# F_-V1.net
KiCad netlist of a schematic drawn in Altium Designer
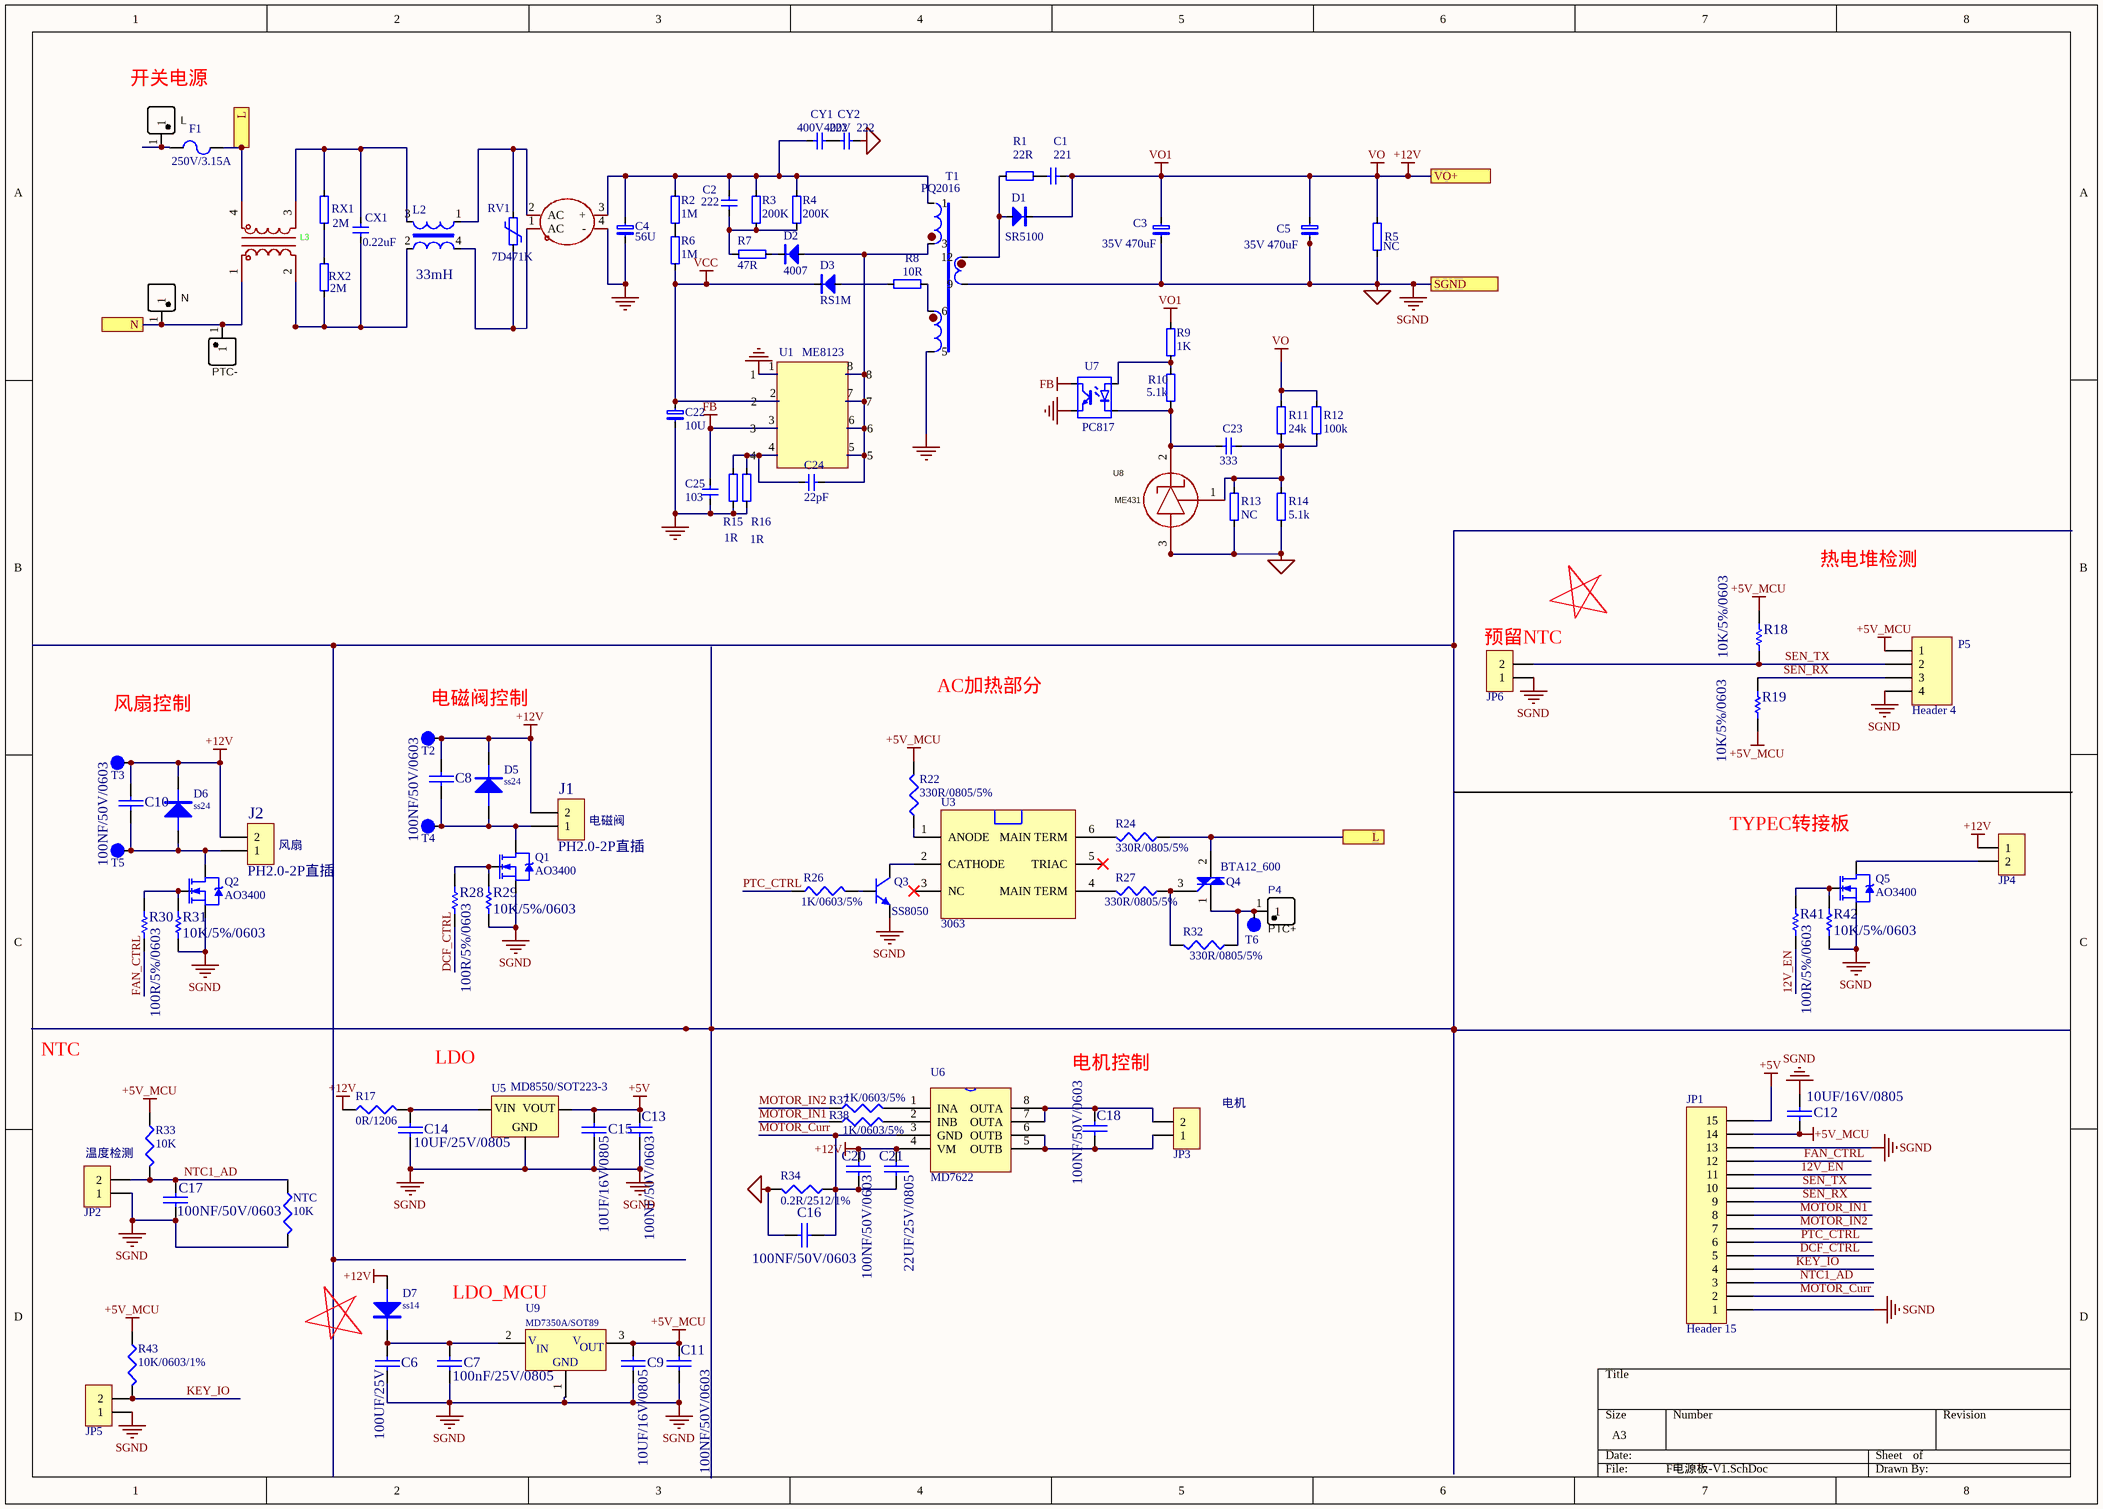
[diagram p0: F电源板-V1.SchDoc]

(export (version "E")
  (design (tool "Eeschema 10.0.6"))
  (components
    (comp (ref "BD1")
      (value "DB107S")
      (footprint "DBS_L8.4-W6.4-P5.10-LS10.2-BL")
      (fields (field (name "MANUFACTURER") "Hottech(合科泰)"))
      (libsource (lib "altium-import") (part "root_2_mirrored_DB107S_C190797_"))
    )
    (comp (ref "C1") (value "221") (footprint "1206c") (description "C？") (libsource (lib "*") (part "C.2")))
    (comp (ref "C2") (value "222") (footprint "1206c") (description "C？") (libsource (lib "*") (part "C.2")))
    (comp (ref "C3")
      (value "35V 470uF")
      (footprint "CAP 5.0*10*16")
      (description "C?")
      (libsource (lib "*") (part "CB.2"))
    )
    (comp (ref "C4")
      (value "56U")
      (footprint "CAP 7.5*16*25")
      (description "C?")
      (libsource (lib "*") (part "CB.2"))
    )
    (comp (ref "C5")
      (value "35V 470uF")
      (footprint "CAP 5.0*10*16")
      (description "C?")
      (libsource (lib "*") (part "CB.2"))
    )
    (comp (ref "C6")
      (value "100UF/25V")
      (footprint "CAP 2.5*5*11")
      (libsource (lib "eric20140112") (part "CAPB"))
    )
    (comp (ref "C7")
      (value "100nF/25V/0805")
      (footprint "C 0805_L")
      (libsource (lib "eric20140112") (part "CAPB"))
    )
    (comp (ref "C8")
      (value "100NF/50V/0603")
      (footprint "C 0603_L")
      (libsource (lib "eric20140112") (part "CAPB"))
    )
    (comp (ref "C9")
      (value "10UF/16V/0805")
      (footprint "C 0805_L")
      (libsource (lib "eric20140112") (part "CAPB"))
    )
    (comp (ref "C10")
      (value "100NF/50V/0603")
      (footprint "C 0603_L")
      (libsource (lib "eric20140112") (part "CAPB"))
    )
    (comp (ref "C11")
      (value "100NF/50V/0603")
      (footprint "C 0603_L")
      (libsource (lib "eric20140112") (part "CAPB"))
    )
    (comp (ref "C12")
      (value "10UF/16V/0805")
      (footprint "C 0805_L")
      (libsource (lib "eric20140112") (part "CAPB"))
    )
    (comp (ref "C13")
      (value "100NF/50V/0603")
      (footprint "C 0603_L")
      (libsource (lib "eric20140112") (part "CAPB"))
    )
    (comp (ref "C14")
      (value "10UF/25V/0805")
      (footprint "C 0805_L")
      (libsource (lib "eric20140112") (part "CAPB"))
    )
    (comp (ref "C15")
      (value "10UF/16V/0805")
      (footprint "C 0805_L")
      (libsource (lib "eric20140112") (part "CAPB"))
    )
    (comp (ref "C16")
      (value "100NF/50V/0603")
      (footprint "C 0603_L")
      (libsource (lib "eric20140112") (part "CAPB"))
    )
    (comp (ref "C17")
      (value "100NF/50V/0603")
      (footprint "C 0603_L")
      (libsource (lib "eric20140112") (part "CAPB"))
    )
    (comp (ref "C18")
      (value "100NF/50V/0603")
      (footprint "C 0603_L")
      (libsource (lib "eric20140112") (part "CAPB"))
    )
    (comp (ref "C20")
      (value "100NF/50V/0603")
      (footprint "C 0603_L")
      (libsource (lib "eric20140112") (part "CAPB"))
    )
    (comp (ref "C21")
      (value "22UF/25V/0805")
      (footprint "0805C-S")
      (libsource (lib "eric20140112") (part "CAPB"))
    )
    (comp (ref "C22")
      (value "10U")
      (footprint "CAP 2.5*5*11 - BK")
      (description "C?")
      (libsource (lib "*") (part "CB.2"))
    )
    (comp (ref "C23") (value "333") (footprint "0805C") (description "C？") (libsource (lib "*") (part "C.2")))
    (comp (ref "C24")
      (value "22pF")
      (footprint "0805C")
      (description "C？")
      (libsource (lib "*") (part "C.2"))
    )
    (comp (ref "C25") (value "103") (footprint "0805C") (description "C？") (libsource (lib "*") (part "C.2")))
    (comp (ref "CX1")
      (value "0.22uF")
      (footprint "CAP-TH_L13.0-W6.0-P10.00-D1.2")
      (description "C？")
      (libsource (lib "*") (part "C.2"))
    )
    (comp (ref "CY1")
      (value "400V  222")
      (footprint "CY2-P10*4.7")
      (description "C？")
      (libsource (lib "*") (part "C.2"))
    )
    (comp (ref "CY2")
      (value "400V  222")
      (footprint "CY2-P10*4.7")
      (description "C？")
      (libsource (lib "*") (part "C.2"))
    )
    (comp (ref "D1") (value "SR5100") (footprint "do-27") (libsource (lib "*") (part "D.2")))
    (comp (ref "D2") (value "4007") (footprint "SMA") (libsource (lib "*") (part "D.2")))
    (comp (ref "D3") (value "RS1M") (footprint "SMA") (libsource (lib "*") (part "D.2")))
    (comp (ref "D5") (value "ss24") (footprint "SOD-123") (libsource (lib "eric20140112") (part "DIODE")))
    (comp (ref "D6") (value "ss24") (footprint "SOD-123") (libsource (lib "eric20140112") (part "DIODE")))
    (comp (ref "D7") (value "ss14") (footprint "SOD-123") (libsource (lib "eric20140112") (part "DIODE")))
    (comp (ref "F1") (value "250V/3.15A") (footprint "MST8*4") (libsource (lib "*") (part "FUSE")))
    (comp (ref "J1")
      (value "PH2.0-2P直插")
      (footprint "PH2.0-LI-2P")
      (libsource (lib "eric20140112") (part "CON2"))
    )
    (comp (ref "J2")
      (value "PH2.0-2P直插")
      (footprint "PH2.0-LI-2P")
      (libsource (lib "eric20140112") (part "CON2"))
    )
    (comp (ref "JP1")
      (value "Header 15")
      (footprint "FPC-SMD_15P-P1.00_XUNPU_FPC-1.0FX-15PWCR-H20")
      (description "Header, 15-Pin")
      (fields (field (name "PUBLISHER") "Altium Limited"))
      (libsource (lib "Miscellaneous Connectors") (part "Header 15"))
    )
    (comp (ref "JP2")
      (value "HDR-1X2")
      (footprint "PH2.0-LI-2P")
      (description "2P接插件")
      (fields (field (name "版权归属") "源创客"))
      (libsource (lib "4.4   - 接插件-脚距2.0") (part "Header 2"))
    )
    (comp (ref "JP3")
      (value "HDR-1X2")
      (footprint "PH2.0-LI-2P")
      (description "2P接插件")
      (fields (field (name "版权归属") "源创客"))
      (libsource (lib "") (part "Header 2_2"))
    )
    (comp (ref "JP4")
      (value "HDR-1X2")
      (footprint "PH2.0-LI-2P")
      (description "2P接插件")
      (fields (field (name "版权归属") "源创客"))
      (libsource (lib "") (part "Header 2_1"))
    )
    (comp (ref "JP5")
      (value "HDR-1X2")
      (footprint "PH2.0-LI-2P")
      (description "2P接插件")
      (fields (field (name "版权归属") "源创客"))
      (libsource (lib "4.4   - 接插件-脚距2.0") (part "Header 2"))
    )
    (comp (ref "JP6")
      (value "HDR-1X2")
      (footprint "PH2.0-LI-2P")
      (description "2P接插件")
      (fields (field (name "版权归属") "源创客"))
      (libsource (lib "4.4   - 接插件-脚距2.0") (part "Header 2"))
    )
    (comp (ref "L2") (value "~") (footprint "UU9.8") (libsource (lib "*") (part "LC.6")))
    (comp (ref "L3")
      (value "PDMCAT953-501MLN")
      (footprint "IND-TH_4P-L12.0-W6.0_PDMCAT953-501MLN")
      (fields (field (name "MANUFACTURER") "PROD(谱罗德)"))
      (libsource (lib "altium-import") (part "root_1_PDMCAT953-501MLN_"))
    )
    (comp (ref "NTC") (value "10K") (footprint "R 0603_L") (libsource (lib "DXPsch") (part "R")))
    (comp (ref "P1")
      (value "L")
      (footprint "4.8*0.8")
      (fields
        (field (name "BOM_SUPPLIER PART") "C9900007423")
        (field (name "BOM_MANUFACTURER PART") "TP-红色测试点")
        (field (name "CONTRIBUTOR") "lcsc")
      )
      (libsource (lib "altium-import") (part "root_3_BAT_"))
    )
    (comp (ref "P2")
      (value "N")
      (footprint "4.8*0.8")
      (fields
        (field (name "BOM_SUPPLIER PART") "C9900007423")
        (field (name "BOM_MANUFACTURER PART") "TP-红色测试点")
        (field (name "CONTRIBUTOR") "lcsc")
      )
      (libsource (lib "altium-import") (part "root_3_BAT_"))
    )
    (comp (ref "P3")
      (value "PTC-")
      (footprint "4.8*0.8")
      (fields
        (field (name "BOM_SUPPLIER PART") "C9900007423")
        (field (name "BOM_MANUFACTURER PART") "TP-红色测试点")
        (field (name "CONTRIBUTOR") "lcsc")
      )
      (libsource (lib "altium-import") (part "root_1_BAT_"))
    )
    (comp (ref "P4")
      (value "PTC+")
      (footprint "4.8*0.8")
      (fields
        (field (name "BOM_SUPPLIER PART") "C9900007423")
        (field (name "BOM_MANUFACTURER PART") "TP-红色测试点")
        (field (name "CONTRIBUTOR") "lcsc")
      )
      (libsource (lib "altium-import") (part "root_2_BAT_"))
    )
    (comp (ref "P5")
      (value "Header 4")
      (footprint "FPC-SMD_FPC-0.5-4P-LTH2.0")
      (description "Header, 4-Pin")
      (fields (field (name "PUBLISHER") "Altium Limited"))
      (libsource (lib "Miscellaneous Connectors") (part "Header 4"))
    )
    (comp (ref "Q1")
      (value "AO3400")
      (footprint "SOT23-3L -big")
      (description "N-Channel Power MOSFET")
      (fields (field (name "PUBLISHER") "Altium Limited"))
      (libsource (lib "eric20140112") (part "NMOS-2"))
    )
    (comp (ref "Q2")
      (value "AO3400")
      (footprint "SOT23-3L -big")
      (description "N-Channel Power MOSFET")
      (fields (field (name "PUBLISHER") "Altium Limited"))
      (libsource (lib "eric20140112") (part "NMOS-2"))
    )
    (comp (ref "Q3")
      (value "SS8050")
      (footprint "SOT23-3N")
      (description "高频放大-NPN型")
      (fields (field (name "版权归属") "源创客"))
      (libsource (lib "6.2   - 三极管") (part "8050-SMD"))
    )
    (comp (ref "Q4")
      (value "BTA12_600")
      (footprint "TO-263AB_L10.0-W9.2-P5.08-LS15.4-BL")
      (description "双向可控硅")
      (fields (field (name "版权归属") "源创客"))
      (libsource (lib "6.1   - 场效应管-可控硅") (part "BTA12_600"))
    )
    (comp (ref "Q5")
      (value "AO3400")
      (footprint "SOT23-3L -big")
      (description "N-Channel Power MOSFET")
      (fields (field (name "PUBLISHER") "Altium Limited"))
      (libsource (lib "eric20140112") (part "NMOS-2"))
    )
    (comp (ref "R1") (value "22R") (footprint "1206r") (libsource (lib "") (part "R.2_1")))
    (comp (ref "R2") (value "1M") (footprint "1206R") (libsource (lib "*") (part "R.2")))
    (comp (ref "R3") (value "200K") (footprint "1206R") (libsource (lib "*") (part "R.2")))
    (comp (ref "R4") (value "200K") (footprint "1206R") (libsource (lib "*") (part "R.2")))
    (comp (ref "R5") (value "NC") (footprint "1206R") (libsource (lib "*") (part "R.2")))
    (comp (ref "R6") (value "1M") (footprint "1206R") (libsource (lib "*") (part "R.2")))
    (comp (ref "R7") (value "47R") (footprint "1206R") (libsource (lib "*") (part "R.2")))
    (comp (ref "R8") (value "10R") (footprint "1206") (libsource (lib "*") (part "R.2")))
    (comp (ref "R9") (value "1K") (footprint "0805R") (libsource (lib "*") (part "R.2")))
    (comp (ref "R10") (value "5.1k") (footprint "0805R") (libsource (lib "*") (part "R.2")))
    (comp (ref "R11") (value "24k") (footprint "0805R") (libsource (lib "*") (part "R.2")))
    (comp (ref "R12") (value "100k") (footprint "0805R") (libsource (lib "*") (part "R.2")))
    (comp (ref "R13") (value "NC") (footprint "0805R") (libsource (lib "*") (part "R.2")))
    (comp (ref "R14") (value "5.1k") (footprint "0805R") (libsource (lib "*") (part "R.2")))
    (comp (ref "R15") (value "1R") (footprint "1206R") (libsource (lib "*") (part "R.2")))
    (comp (ref "R16") (value "1R") (footprint "1206R") (libsource (lib "*") (part "R.2")))
    (comp (ref "R17") (value "0R/1206") (footprint "1206r") (libsource (lib "DXPsch") (part "R")))
    (comp (ref "R18")
      (value "10K/5%/0603")
      (footprint "0603R")
      (libsource (lib "eric20140112") (part "RESA"))
    )
    (comp (ref "R19")
      (value "10K/5%/0603")
      (footprint "0603R")
      (libsource (lib "eric20140112") (part "RESA"))
    )
    (comp (ref "R22") (value "330R/0805/5%") (footprint "0805R") (libsource (lib "DXPsch") (part "R")))
    (comp (ref "R24") (value "330R/0805/5%") (footprint "0805R") (libsource (lib "DXPsch") (part "R")))
    (comp (ref "R26") (value "1K/0603/5%") (footprint "R 0603_L") (libsource (lib "DXPsch") (part "R")))
    (comp (ref "R27") (value "330R/0805/5%") (footprint "0805R") (libsource (lib "DXPsch") (part "R")))
    (comp (ref "R28")
      (value "100R/5%/0603")
      (footprint "0603R")
      (libsource (lib "eric20140112") (part "RESA"))
    )
    (comp (ref "R29")
      (value "10K/5%/0603")
      (footprint "0603R")
      (libsource (lib "eric20140112") (part "RESA"))
    )
    (comp (ref "R30")
      (value "100R/5%/0603")
      (footprint "0603R")
      (libsource (lib "eric20140112") (part "RESA"))
    )
    (comp (ref "R31")
      (value "10K/5%/0603")
      (footprint "0603R")
      (libsource (lib "eric20140112") (part "RESA"))
    )
    (comp (ref "R32") (value "330R/0805/5%") (footprint "0805R") (libsource (lib "DXPsch") (part "R")))
    (comp (ref "R33") (value "10K") (footprint "R 0603_L") (libsource (lib "DXPsch") (part "R")))
    (comp (ref "R34") (value "0.2R/2512/1%") (footprint "R 2512_L") (libsource (lib "DXPsch") (part "R")))
    (comp (ref "R37") (value "1K/0603/5%") (footprint "R 0603_L") (libsource (lib "DXPsch") (part "R")))
    (comp (ref "R38") (value "1K/0603/5%") (footprint "R 0603_L") (libsource (lib "DXPsch") (part "R")))
    (comp (ref "R41")
      (value "100R/5%/0603")
      (footprint "0603R")
      (libsource (lib "eric20140112") (part "RESA"))
    )
    (comp (ref "R42")
      (value "10K/5%/0603")
      (footprint "0603R")
      (libsource (lib "eric20140112") (part "RESA"))
    )
    (comp (ref "R43") (value "10K/0603/1%") (footprint "R 0603_L") (libsource (lib "DXPsch") (part "R")))
    (comp (ref "RV1") (value "7D471K") (footprint "VDR 7D-5") (libsource (lib "*") (part "RM")))
    (comp (ref "RX1") (value "2M") (footprint "1206R") (libsource (lib "") (part "R.2_1")))
    (comp (ref "RX2") (value "2M") (footprint "1206R") (libsource (lib "") (part "R.2_1")))
    (comp (ref "T1") (value "PQ2016") (footprint "EE1610") (libsource (lib "*") (part "T.6")))
    (comp (ref "T2")
      (value "TP")
      (footprint "TP_2.0mm")
      (libsource (lib "Miscellaneous Devices") (part "TP"))
    )
    (comp (ref "T3")
      (value "TP")
      (footprint "TP_2.0mm")
      (libsource (lib "Miscellaneous Devices") (part "TP"))
    )
    (comp (ref "T4")
      (value "TP")
      (footprint "TP_2.0mm")
      (libsource (lib "Miscellaneous Devices") (part "TP"))
    )
    (comp (ref "T5")
      (value "TP")
      (footprint "TP_2.0mm")
      (libsource (lib "Miscellaneous Devices") (part "TP"))
    )
    (comp (ref "T6")
      (value "TP")
      (footprint "TP_2.0mm")
      (libsource (lib "Miscellaneous Devices") (part "TP"))
    )
    (comp (ref "U1") (value "ME8123") (footprint "DIP8") (libsource (lib "*") (part "8603")))
    (comp (ref "U3")
      (value "3063")
      (footprint "SMD-6_L7.3-W6.5-P2.54-LS10.2-BL")
      (libsource (lib "*") (part "MOC3021"))
    )
    (comp (ref "U5")
      (value "MD8550/SOT223-3")
      (footprint "SOT-223")
      (libsource (lib "HL-6022充电控制PCB_Project") (part "AMS1117-3.3V"))
    )
    (comp (ref "U6") (value "MD7622") (footprint "SOP8_N") (libsource (lib "常用SCH") (part "013a_1")))
    (comp (ref "U7") (value "PC817") (footprint "SMD-4") (libsource (lib "*") (part "OP")))
    (comp (ref "U8")
      (value "ME431")
      (footprint "SOT-23-3_ME431")
      (fields (field (name "MANUFACTURER") "MICRONE(南京微盟)") (field (name "MANUFACTURER PART") "ME431AXG"))
      (libsource (lib "altium-import") (part "root_0_mirrored_ME431AXG_"))
    )
    (comp (ref "U9")
      (value "MD7350A/SOT89")
      (footprint "SOT89_M")
      (libsource (lib "eric20170915") (part "ME6118A_SOT89"))
    )
  )
  (nets
    (net (code "1") (name "+5V") (class "Default")
      (node (ref "C13") (pin "2") (pintype "passive"))
      (node (ref "C15") (pin "1") (pintype "passive"))
      (node (ref "JP1") (pin "15") (pinfunction "15_15") (pintype "passive"))
      (node (ref "U5") (pin "3") (pinfunction "VOUT_3") (pintype "passive"))
    )
    (net (code "2") (name "+5V_MCU") (class "Default")
      (node (ref "C11") (pin "2") (pintype "passive"))
      (node (ref "C12") (pin "2") (pintype "passive"))
      (node (ref "C9") (pin "1") (pintype "passive"))
      (node (ref "JP1") (pin "14") (pinfunction "14_14") (pintype "passive"))
      (node (ref "P5") (pin "1") (pinfunction "1_1") (pintype "passive"))
      (node (ref "R18") (pin "2") (pinfunction "2_2") (pintype "passive"))
      (node (ref "R19") (pin "1") (pinfunction "1_1") (pintype "passive"))
      (node (ref "R22") (pin "2") (pintype "passive"))
      (node (ref "R33") (pin "1") (pintype "passive"))
      (node (ref "R43") (pin "1") (pintype "passive"))
      (node (ref "U9") (pin "3") (pinfunction "VIN_3") (pintype "passive"))
    )
    (net (code "3") (name "+12V") (class "Default")
      (node (ref "C1") (pin "2") (pintype "passive"))
      (node (ref "C10") (pin "1") (pintype "passive"))
      (node (ref "C20") (pin "2") (pintype "passive"))
      (node (ref "C21") (pin "1") (pintype "passive"))
      (node (ref "C3") (pin "1") (pintype "passive"))
      (node (ref "C5") (pin "1") (pintype "passive"))
      (node (ref "C8") (pin "1") (pintype "passive"))
      (node (ref "D1") (pin "2") (pintype "passive"))
      (node (ref "D5") (pin "2") (pinfunction "K_2") (pintype "passive"))
      (node (ref "D6") (pin "2") (pinfunction "K_2") (pintype "passive"))
      (node (ref "D7") (pin "1") (pinfunction "A_1") (pintype "passive"))
      (node (ref "J1") (pin "2") (pinfunction "2_2") (pintype "passive"))
      (node (ref "J2") (pin "2") (pinfunction "2_2") (pintype "passive"))
      (node (ref "JP4") (pin "1") (pinfunction "1_1") (pintype "passive"))
      (node (ref "R11") (pin "1") (pintype "passive"))
      (node (ref "R12") (pin "1") (pintype "passive"))
      (node (ref "R17") (pin "1") (pintype "passive"))
      (node (ref "R5") (pin "2") (pintype "passive"))
      (node (ref "R9") (pin "2") (pintype "passive"))
      (node (ref "T2") (pin "1") (pintype "passive"))
      (node (ref "T3") (pin "1") (pintype "passive"))
      (node (ref "U6") (pin "4") (pinfunction "VM_4") (pintype "passive"))
    )
    (net (code "4") (name "/12V_EN") (class "Default")
      (node (ref "JP1") (pin "11") (pinfunction "11_11") (pintype "passive"))
      (node (ref "R41") (pin "1") (pinfunction "1_1") (pintype "passive"))
    )
    (net (code "5") (name "/DCF_CTRL") (class "Default")
      (node (ref "JP1") (pin "5") (pinfunction "5_5") (pintype "passive"))
      (node (ref "R28") (pin "1") (pinfunction "1_1") (pintype "passive"))
    )
    (net (code "6") (name "/FAN_CTRL") (class "Default")
      (node (ref "JP1") (pin "12") (pinfunction "12_12") (pintype "passive"))
      (node (ref "R30") (pin "1") (pinfunction "1_1") (pintype "passive"))
    )
    (net (code "7") (name "/KEY_IO") (class "Default")
      (node (ref "JP1") (pin "4") (pinfunction "4_4") (pintype "passive"))
      (node (ref "JP5") (pin "2") (pinfunction "2_2") (pintype "passive"))
      (node (ref "R43") (pin "2") (pintype "passive"))
    )
    (net (code "8") (name "/L") (class "Default")
      (node (ref "F1") (pin "1") (pinfunction "1_1") (pintype "passive"))
      (node (ref "L3") (pin "4") (pinfunction "4_4") (pintype "passive"))
      (node (ref "Q4") (pin "2") (pinfunction "A2_2") (pintype "passive"))
      (node (ref "R24") (pin "1") (pintype "passive"))
    )
    (net (code "9") (name "/MOTOR_Curr") (class "Default")
      (node (ref "C16") (pin "1") (pintype "passive"))
      (node (ref "C20") (pin "1") (pintype "passive"))
      (node (ref "C21") (pin "2") (pintype "passive"))
      (node (ref "JP1") (pin "2") (pinfunction "2_2") (pintype "passive"))
      (node (ref "R34") (pin "1") (pintype "passive"))
      (node (ref "U6") (pin "3") (pinfunction "GND_3") (pintype "passive"))
    )
    (net (code "10") (name "/MOTOR_IN1") (class "Default")
      (node (ref "JP1") (pin "8") (pinfunction "8_8") (pintype "passive"))
      (node (ref "R38") (pin "1") (pintype "passive"))
    )
    (net (code "11") (name "/MOTOR_IN2") (class "Default")
      (node (ref "JP1") (pin "7") (pinfunction "7_7") (pintype "passive"))
      (node (ref "R37") (pin "1") (pintype "passive"))
    )
    (net (code "12") (name "/N") (class "Default")
      (node (ref "L3") (pin "1") (pinfunction "1_1") (pintype "passive"))
      (node (ref "P2") (pin "1") (pinfunction "1_1") (pintype "passive"))
      (node (ref "P3") (pin "1") (pinfunction "1_1") (pintype "passive"))
    )
    (net (code "13") (name "/NTC1_AD") (class "Default")
      (node (ref "C17") (pin "1") (pintype "passive"))
      (node (ref "JP1") (pin "3") (pinfunction "3_3") (pintype "passive"))
      (node (ref "JP2") (pin "2") (pinfunction "2_2") (pintype "passive"))
      (node (ref "NTC") (pin "1") (pintype "passive"))
      (node (ref "R33") (pin "2") (pintype "passive"))
    )
    (net (code "14") (name "/PTC_CTRL") (class "Default")
      (node (ref "JP1") (pin "6") (pinfunction "6_6") (pintype "passive"))
      (node (ref "R26") (pin "1") (pintype "passive"))
    )
    (net (code "15") (name "/SEN_RX") (class "Default")
      (node (ref "JP1") (pin "9") (pinfunction "9_9") (pintype "passive"))
      (node (ref "P5") (pin "3") (pinfunction "3_3") (pintype "passive"))
      (node (ref "R19") (pin "2") (pinfunction "2_2") (pintype "passive"))
    )
    (net (code "16") (name "/SEN_TX") (class "Default")
      (node (ref "JP1") (pin "10") (pinfunction "10_10") (pintype "passive"))
      (node (ref "JP6") (pin "2") (pinfunction "2_2") (pintype "passive"))
      (node (ref "P5") (pin "2") (pinfunction "2_2") (pintype "passive"))
      (node (ref "R18") (pin "1") (pinfunction "1_1") (pintype "passive"))
    )
    (net (code "17") (name "FB") (class "Default")
      (node (ref "C25") (pin "1") (pintype "passive"))
      (node (ref "U1") (pin "3") (pinfunction "3_3") (pintype "passive"))
      (node (ref "U7") (pin "4") (pintype "passive"))
    )
    (net (code "18") (name "GND") (class "Default")
      (node (ref "BD1") (pin "4") (pinfunction "-_4") (pintype "passive"))
      (node (ref "C22") (pin "2") (pintype "passive"))
      (node (ref "C25") (pin "2") (pintype "passive"))
      (node (ref "C4") (pin "2") (pintype "passive"))
      (node (ref "R15") (pin "1") (pintype "passive"))
      (node (ref "R16") (pin "1") (pintype "passive"))
      (node (ref "T1") (pin "5") (pinfunction "5_5") (pintype "passive"))
      (node (ref "U1") (pin "1") (pinfunction "1_1") (pintype "passive"))
      (node (ref "U7") (pin "3") (pintype "passive"))
    )
    (net (code "19") (name "Net-(BD1-+)") (class "Default")
      (node (ref "BD1") (pin "3") (pinfunction "+_3") (pintype "passive"))
      (node (ref "C2") (pin "2") (pintype "passive"))
      (node (ref "C4") (pin "1") (pintype "passive"))
      (node (ref "CY1") (pin "1") (pintype "passive"))
      (node (ref "R2") (pin "1") (pintype "passive"))
      (node (ref "R3") (pin "1") (pintype "passive"))
      (node (ref "R4") (pin "1") (pintype "passive"))
      (node (ref "T1") (pin "1") (pinfunction "1_1") (pintype "passive"))
    )
    (net (code "20") (name "Net-(BD1-AC-Pad1)") (class "Default")
      (node (ref "BD1") (pin "1") (pinfunction "AC_1") (pintype "passive"))
      (node (ref "L2") (pin "4") (pintype "passive"))
      (node (ref "RV1") (pin "1") (pintype "passive"))
    )
    (net (code "21") (name "Net-(BD1-AC-Pad2)") (class "Default")
      (node (ref "BD1") (pin "2") (pinfunction "AC_2") (pintype "passive"))
      (node (ref "L2") (pin "1") (pintype "passive"))
      (node (ref "RV1") (pin "2") (pintype "passive"))
    )
    (net (code "22") (name "Net-(C1-Pad1)") (class "Default")
      (node (ref "C1") (pin "1") (pintype "passive"))
      (node (ref "R1") (pin "2") (pintype "passive"))
    )
    (net (code "23") (name "Net-(C2-Pad1)") (class "Default")
      (node (ref "C2") (pin "1") (pintype "passive"))
      (node (ref "R3") (pin "2") (pintype "passive"))
      (node (ref "R4") (pin "2") (pintype "passive"))
      (node (ref "R7") (pin "2") (pintype "passive"))
    )
    (net (code "24") (name "Net-(C18-Pad1)") (class "Default")
      (node (ref "C18") (pin "1") (pintype "passive"))
      (node (ref "JP3") (pin "1") (pinfunction "1_1") (pintype "passive"))
      (node (ref "U6") (pin "5") (pinfunction "OUTB_5") (pintype "passive"))
      (node (ref "U6") (pin "6") (pinfunction "OUTB_6") (pintype "passive"))
    )
    (net (code "25") (name "Net-(C18-Pad2)") (class "Default")
      (node (ref "C18") (pin "2") (pintype "passive"))
      (node (ref "JP3") (pin "2") (pinfunction "2_2") (pintype "passive"))
      (node (ref "U6") (pin "7") (pinfunction "OUTA_7") (pintype "passive"))
      (node (ref "U6") (pin "8") (pinfunction "OUTA_8") (pintype "passive"))
    )
    (net (code "26") (name "Net-(C24-Pad1)") (class "Default")
      (node (ref "C24") (pin "1") (pintype "passive"))
      (node (ref "R15") (pin "2") (pintype "passive"))
      (node (ref "R16") (pin "2") (pintype "passive"))
      (node (ref "U1") (pin "4") (pinfunction "4_4") (pintype "passive"))
    )
    (net (code "27") (name "Net-(C24-Pad2)") (class "Default")
      (node (ref "C24") (pin "2") (pintype "passive"))
      (node (ref "D2") (pin "1") (pintype "passive"))
      (node (ref "T1") (pin "3") (pinfunction "3_3") (pintype "passive"))
      (node (ref "U1") (pin "5") (pinfunction "5_5") (pintype "passive"))
      (node (ref "U1") (pin "6") (pinfunction "6_6") (pintype "passive"))
      (node (ref "U1") (pin "7") (pinfunction "7_7") (pintype "passive"))
      (node (ref "U1") (pin "8") (pinfunction "8_8") (pintype "passive"))
    )
    (net (code "28") (name "Net-(CX1-Pad1)") (class "Default")
      (node (ref "CX1") (pin "1") (pintype "passive"))
      (node (ref "L2") (pin "2") (pintype "passive"))
      (node (ref "L3") (pin "2") (pinfunction "2_2") (pintype "passive"))
      (node (ref "RX2") (pin "1") (pintype "passive"))
    )
    (net (code "29") (name "Net-(CX1-Pad2)") (class "Default")
      (node (ref "CX1") (pin "2") (pintype "passive"))
      (node (ref "L2") (pin "3") (pintype "passive"))
      (node (ref "L3") (pin "3") (pinfunction "3_3") (pintype "passive"))
      (node (ref "RX1") (pin "2") (pintype "passive"))
    )
    (net (code "30") (name "Net-(CY1-Pad2)") (class "Default")
      (node (ref "CY1") (pin "2") (pintype "passive"))
      (node (ref "CY2") (pin "1") (pintype "passive"))
    )
    (net (code "31") (name "Net-(D1-Pad1)") (class "Default")
      (node (ref "D1") (pin "1") (pintype "passive"))
      (node (ref "R1") (pin "1") (pintype "passive"))
      (node (ref "T1") (pin "12") (pinfunction "12_12") (pintype "passive"))
    )
    (net (code "32") (name "Net-(D2-Pad2)") (class "Default")
      (node (ref "D2") (pin "2") (pintype "passive"))
      (node (ref "R7") (pin "1") (pintype "passive"))
    )
    (net (code "33") (name "Net-(D3-Pad1)") (class "Default")
      (node (ref "D3") (pin "1") (pintype "passive"))
      (node (ref "R8") (pin "1") (pintype "passive"))
    )
    (net (code "34") (name "Net-(D5-A)") (class "Default")
      (node (ref "C8") (pin "2") (pintype "passive"))
      (node (ref "D5") (pin "1") (pinfunction "A_1") (pintype "passive"))
      (node (ref "J1") (pin "1") (pinfunction "1_1") (pintype "passive"))
      (node (ref "Q1") (pin "3") (pinfunction "D_3") (pintype "passive"))
      (node (ref "T4") (pin "1") (pintype "passive"))
    )
    (net (code "35") (name "Net-(D6-A)") (class "Default")
      (node (ref "C10") (pin "2") (pintype "passive"))
      (node (ref "D6") (pin "1") (pinfunction "A_1") (pintype "passive"))
      (node (ref "J2") (pin "1") (pinfunction "1_1") (pintype "passive"))
      (node (ref "Q2") (pin "3") (pinfunction "D_3") (pintype "passive"))
      (node (ref "T5") (pin "1") (pintype "passive"))
    )
    (net (code "36") (name "Net-(D7-K)") (class "Default")
      (node (ref "C6") (pin "1") (pintype "passive"))
      (node (ref "C7") (pin "1") (pintype "passive"))
      (node (ref "D7") (pin "2") (pinfunction "K_2") (pintype "passive"))
      (node (ref "U9") (pin "2") (pinfunction "VOUT_2") (pintype "passive"))
    )
    (net (code "37") (name "Net-(F1-Pad2)") (class "Default")
      (node (ref "F1") (pin "2") (pinfunction "2_2") (pintype "passive"))
      (node (ref "P1") (pin "1") (pinfunction "1_1") (pintype "passive"))
    )
    (net (code "38") (name "Net-(Q1-G)") (class "Default")
      (node (ref "Q1") (pin "1") (pinfunction "G_1") (pintype "passive"))
      (node (ref "R28") (pin "2") (pinfunction "2_2") (pintype "passive"))
      (node (ref "R29") (pin "2") (pinfunction "2_2") (pintype "passive"))
    )
    (net (code "39") (name "Net-(Q2-G)") (class "Default")
      (node (ref "Q2") (pin "1") (pinfunction "G_1") (pintype "passive"))
      (node (ref "R30") (pin "2") (pinfunction "2_2") (pintype "passive"))
      (node (ref "R31") (pin "2") (pinfunction "2_2") (pintype "passive"))
    )
    (net (code "40") (name "Net-(Q3-B)") (class "Default")
      (node (ref "Q3") (pin "1") (pinfunction "B_1") (pintype "passive"))
      (node (ref "R26") (pin "2") (pintype "passive"))
    )
    (net (code "41") (name "Net-(Q3-C)") (class "Default")
      (node (ref "Q3") (pin "3") (pinfunction "C_3") (pintype "passive"))
      (node (ref "U3") (pin "2") (pinfunction "CATHODE_2") (pintype "passive"))
    )
    (net (code "42") (name "Net-(Q4-A1)") (class "Default")
      (node (ref "P4") (pin "1") (pinfunction "1_1") (pintype "passive"))
      (node (ref "Q4") (pin "1") (pinfunction "A1_1") (pintype "passive"))
      (node (ref "R32") (pin "1") (pintype "passive"))
      (node (ref "T6") (pin "1") (pintype "passive"))
    )
    (net (code "43") (name "Net-(Q4-G)") (class "Default")
      (node (ref "Q4") (pin "3") (pinfunction "G_3") (pintype "passive"))
      (node (ref "R27") (pin "1") (pintype "passive"))
      (node (ref "R32") (pin "2") (pintype "passive"))
    )
    (net (code "44") (name "Net-(Q5-D)") (class "Default")
      (node (ref "JP4") (pin "2") (pinfunction "2_2") (pintype "passive"))
      (node (ref "Q5") (pin "3") (pinfunction "D_3") (pintype "passive"))
    )
    (net (code "45") (name "Net-(Q5-G)") (class "Default")
      (node (ref "Q5") (pin "1") (pinfunction "G_1") (pintype "passive"))
      (node (ref "R41") (pin "2") (pinfunction "2_2") (pintype "passive"))
      (node (ref "R42") (pin "2") (pinfunction "2_2") (pintype "passive"))
    )
    (net (code "46") (name "Net-(R2-Pad2)") (class "Default")
      (node (ref "R2") (pin "2") (pintype "passive"))
      (node (ref "R6") (pin "1") (pintype "passive"))
    )
    (net (code "47") (name "Net-(R8-Pad2)") (class "Default")
      (node (ref "R8") (pin "2") (pintype "passive"))
      (node (ref "T1") (pin "6") (pinfunction "6_6") (pintype "passive"))
    )
    (net (code "48") (name "Net-(R10-Pad2)") (class "Default")
      (node (ref "R10") (pin "2") (pintype "passive"))
      (node (ref "R9") (pin "1") (pintype "passive"))
      (node (ref "U7") (pin "1") (pintype "passive"))
    )
    (net (code "49") (name "Net-(R24-Pad2)") (class "Default")
      (node (ref "R24") (pin "2") (pintype "passive"))
      (node (ref "U3") (pin "6") (pinfunction "MAIN_TERM_6") (pintype "passive"))
    )
    (net (code "50") (name "Net-(R27-Pad2)") (class "Default")
      (node (ref "R27") (pin "2") (pintype "passive"))
      (node (ref "U3") (pin "4") (pinfunction "MAIN_TERM_4") (pintype "passive"))
    )
    (net (code "51") (name "Net-(RX1-Pad1)") (class "Default")
      (node (ref "RX1") (pin "1") (pintype "passive"))
      (node (ref "RX2") (pin "2") (pintype "passive"))
    )
    (net (code "52") (name "Net-(U3-ANODE)") (class "Default")
      (node (ref "R22") (pin "1") (pintype "passive"))
      (node (ref "U3") (pin "1") (pinfunction "ANODE_1") (pintype "passive"))
    )
    (net (code "53") (name "Net-(U5-VIN)") (class "Default")
      (node (ref "C14") (pin "1") (pintype "passive"))
      (node (ref "R17") (pin "2") (pintype "passive"))
      (node (ref "U5") (pin "1") (pinfunction "VIN_1") (pintype "passive"))
    )
    (net (code "54") (name "Net-(U6-INA)") (class "Default")
      (node (ref "R37") (pin "2") (pintype "passive"))
      (node (ref "U6") (pin "1") (pinfunction "INA_1") (pintype "passive"))
    )
    (net (code "55") (name "Net-(U6-INB)") (class "Default")
      (node (ref "R38") (pin "2") (pintype "passive"))
      (node (ref "U6") (pin "2") (pinfunction "INB_2") (pintype "passive"))
    )
    (net (code "56") (name "Net-(U8-C)") (class "Default")
      (node (ref "C23") (pin "1") (pintype "passive"))
      (node (ref "R10") (pin "1") (pintype "passive"))
      (node (ref "U7") (pin "2") (pintype "passive"))
      (node (ref "U8") (pin "2") (pinfunction "C_2") (pintype "passive"))
    )
    (net (code "57") (name "Net-(U8-REF)") (class "Default")
      (node (ref "C23") (pin "2") (pintype "passive"))
      (node (ref "R11") (pin "2") (pintype "passive"))
      (node (ref "R12") (pin "2") (pintype "passive"))
      (node (ref "R13") (pin "1") (pintype "passive"))
      (node (ref "R14") (pin "1") (pintype "passive"))
      (node (ref "U8") (pin "1") (pinfunction "REF_1") (pintype "passive"))
    )
    (net (code "58") (name "SGND") (class "Default")
      (node (ref "C11") (pin "1") (pintype "passive"))
      (node (ref "C12") (pin "1") (pintype "passive"))
      (node (ref "C13") (pin "1") (pintype "passive"))
      (node (ref "C14") (pin "2") (pintype "passive"))
      (node (ref "C15") (pin "2") (pintype "passive"))
      (node (ref "C16") (pin "2") (pintype "passive"))
      (node (ref "C17") (pin "2") (pintype "passive"))
      (node (ref "C3") (pin "2") (pintype "passive"))
      (node (ref "C5") (pin "2") (pintype "passive"))
      (node (ref "C6") (pin "2") (pintype "passive"))
      (node (ref "C7") (pin "2") (pintype "passive"))
      (node (ref "C9") (pin "2") (pintype "passive"))
      (node (ref "CY2") (pin "2") (pintype "passive"))
      (node (ref "JP1") (pin "1") (pinfunction "1_1") (pintype "passive"))
      (node (ref "JP1") (pin "13") (pinfunction "13_13") (pintype "passive"))
      (node (ref "JP2") (pin "1") (pinfunction "1_1") (pintype "passive"))
      (node (ref "JP5") (pin "1") (pinfunction "1_1") (pintype "passive"))
      (node (ref "JP6") (pin "1") (pinfunction "1_1") (pintype "passive"))
      (node (ref "NTC") (pin "2") (pintype "passive"))
      (node (ref "P5") (pin "4") (pinfunction "4_4") (pintype "passive"))
      (node (ref "Q1") (pin "2") (pinfunction "S_2") (pintype "passive"))
      (node (ref "Q2") (pin "2") (pinfunction "S_2") (pintype "passive"))
      (node (ref "Q3") (pin "2") (pinfunction "E_2") (pintype "passive"))
      (node (ref "Q5") (pin "2") (pinfunction "S_2") (pintype "passive"))
      (node (ref "R13") (pin "2") (pintype "passive"))
      (node (ref "R14") (pin "2") (pintype "passive"))
      (node (ref "R29") (pin "1") (pinfunction "1_1") (pintype "passive"))
      (node (ref "R31") (pin "1") (pinfunction "1_1") (pintype "passive"))
      (node (ref "R34") (pin "2") (pintype "passive"))
      (node (ref "R42") (pin "1") (pinfunction "1_1") (pintype "passive"))
      (node (ref "R5") (pin "1") (pintype "passive"))
      (node (ref "T1") (pin "9") (pinfunction "9_9") (pintype "passive"))
      (node (ref "U5") (pin "2") (pinfunction "GND_2") (pintype "passive"))
      (node (ref "U8") (pin "3") (pinfunction "A_3") (pintype "passive"))
      (node (ref "U9") (pin "1") (pinfunction "GND_1") (pintype "passive"))
    )
    (net (code "59") (name "VCC") (class "Default")
      (node (ref "C22") (pin "1") (pintype "passive"))
      (node (ref "D3") (pin "2") (pintype "passive"))
      (node (ref "R6") (pin "2") (pintype "passive"))
      (node (ref "U1") (pin "2") (pinfunction "2_2") (pintype "passive"))
    )
    (net (code "60") (name "unconnected-(U3-NC-Pad3)") (class "Default")
      (node (ref "U3") (pin "3") (pinfunction "NC_3") (pintype "passive+no_connect"))
    )
    (net (code "61") (name "unconnected-(U3-TRIAC-Pad5)") (class "Default")
      (node (ref "U3") (pin "5") (pinfunction "TRIAC_5") (pintype "passive+no_connect"))
    )
  )
)
